# pcb.net
KiCad netlist of a schematic drawn in Altium Designer
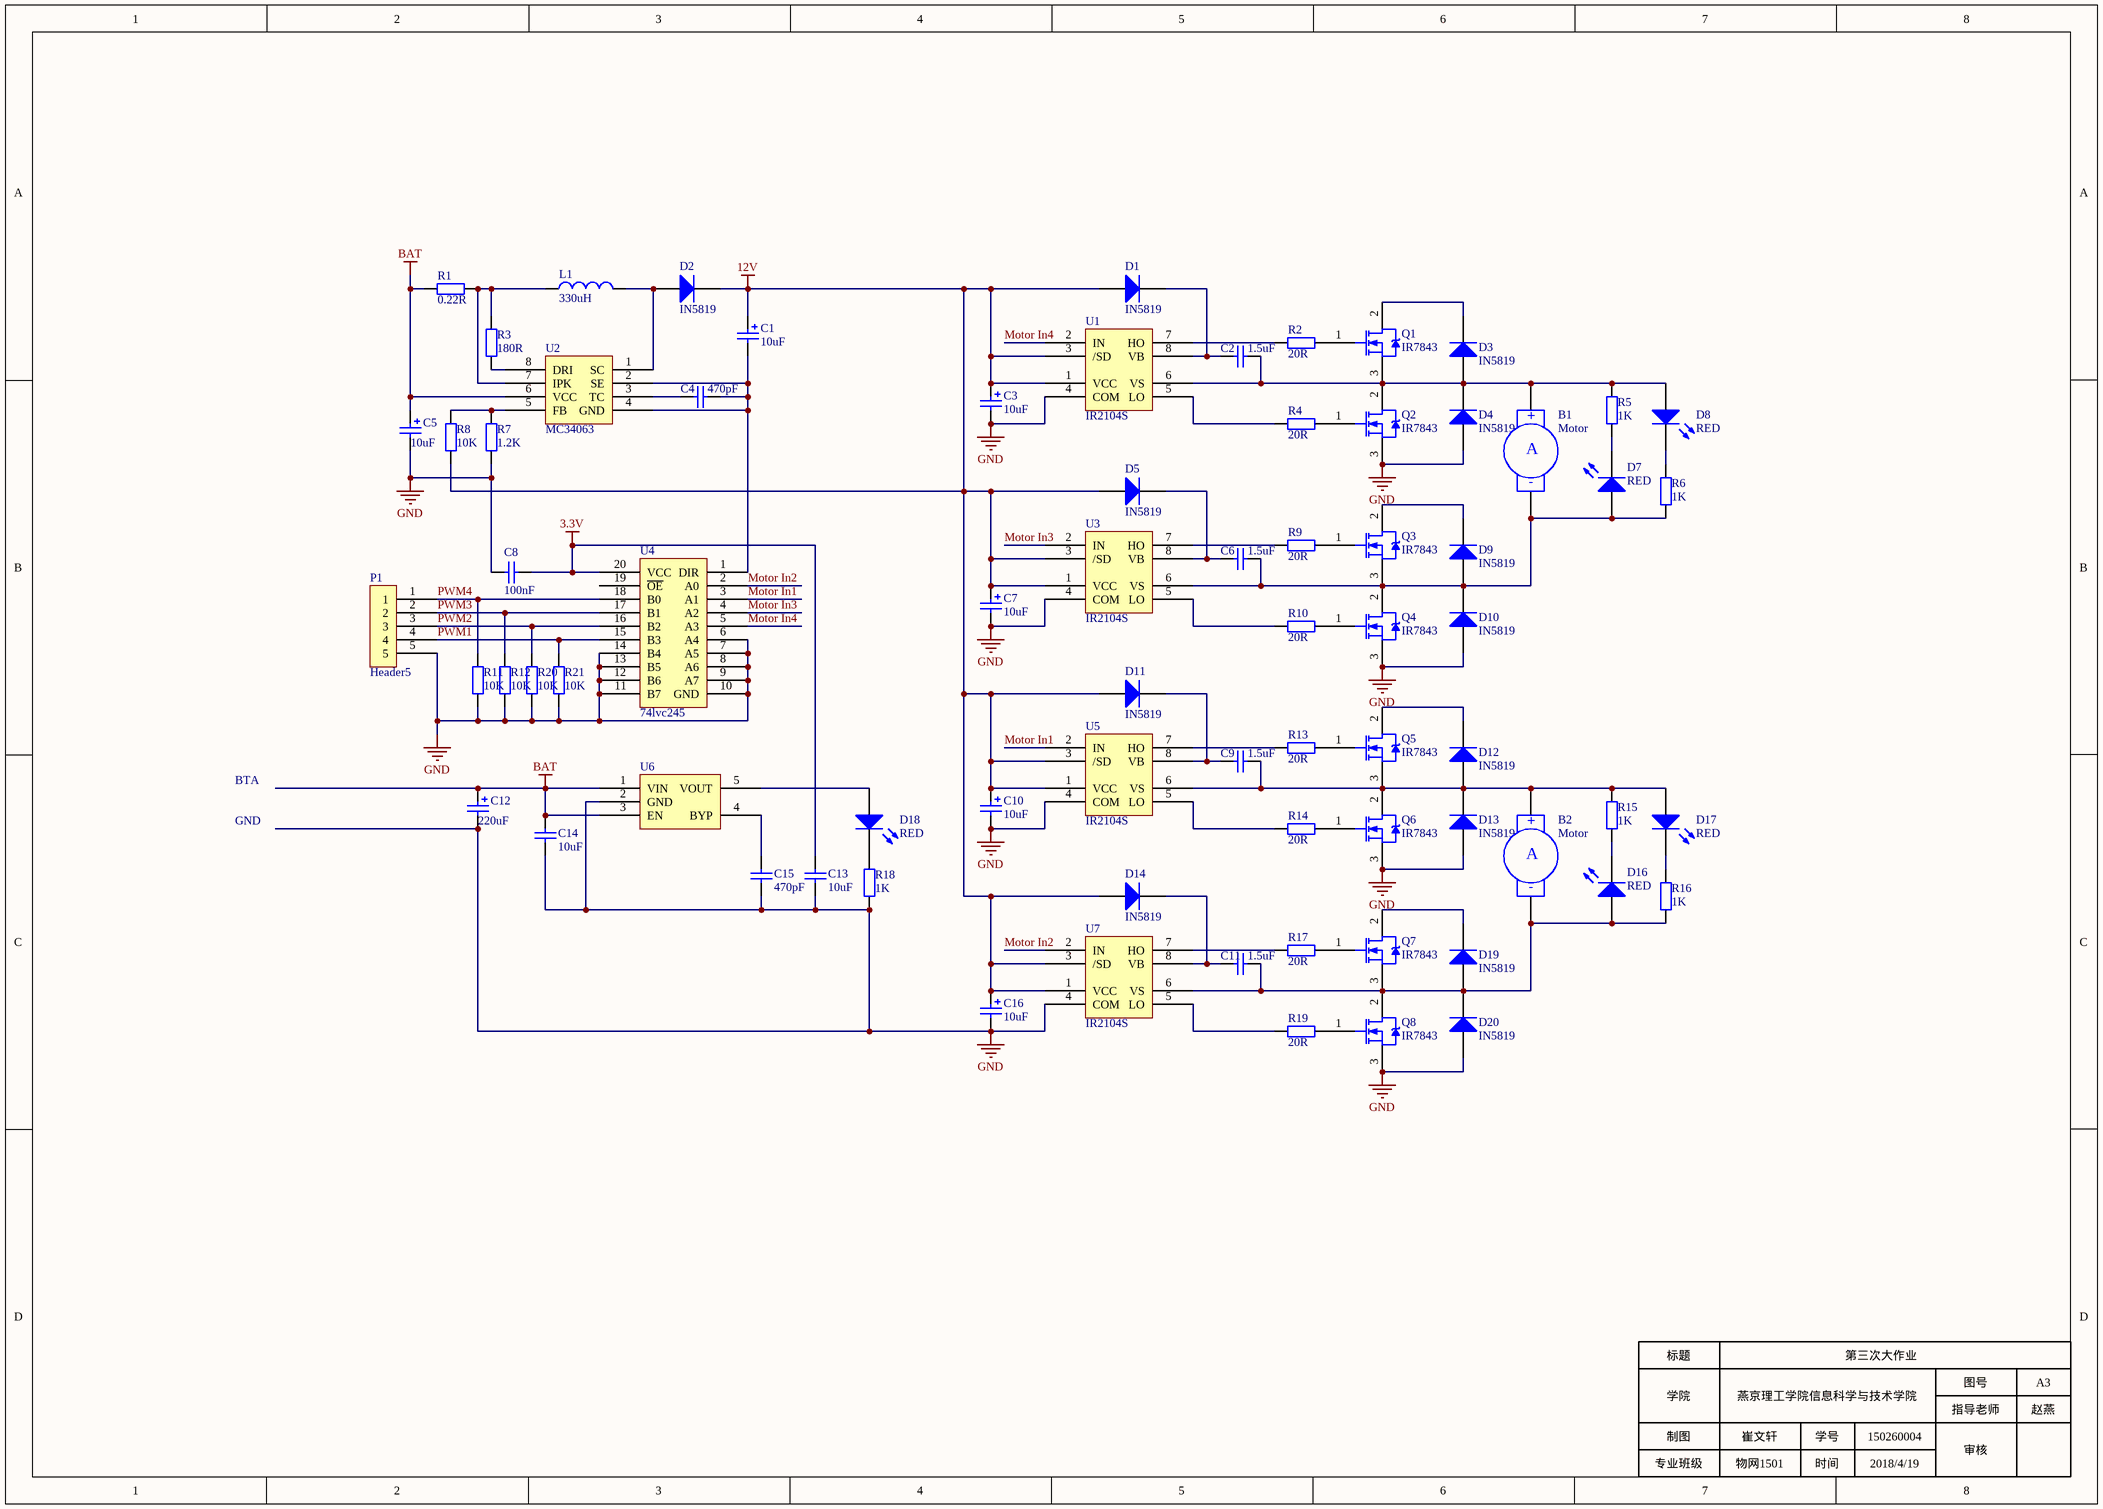
[diagram p0: pcb大作业.SchDoc]

(export (version "E")
  (design (tool "Eeschema 10.0.6"))
  (components
    (comp (ref "B1")
      (value "Motor")
      (footprint "RAD-0.4")
      (description "Servo Motor")
      (fields (field (name "PUBLISHER") "Altium Limited"))
      (libsource (lib "Miscellaneous Devices") (part "Motor Servo"))
    )
    (comp (ref "B2")
      (value "Motor")
      (footprint "RAD-0.4")
      (description "Servo Motor")
      (fields (field (name "PUBLISHER") "Altium Limited"))
      (libsource (lib "Miscellaneous Devices") (part "Motor Servo"))
    )
    (comp (ref "C1")
      (value "10uF")
      (footprint "POLAR0.8")
      (description "Polarized Capacitor (Axial)")
      (fields (field (name "Comment") "Cap Pol2") (field (name "PUBLISHER") "Altium Limited"))
      (libsource (lib "Miscellaneous Devices") (part "Cap Pol2"))
    )
    (comp (ref "C2")
      (value "1.5uF")
      (footprint "RAD-0.3")
      (description "Capacitor")
      (fields (field (name "Comment") "Cap") (field (name "PUBLISHER") "Altium Limited"))
      (libsource (lib "Miscellaneous Devices") (part "Cap"))
    )
    (comp (ref "C3")
      (value "10uF")
      (footprint "POLAR0.8")
      (description "Polarized Capacitor (Axial)")
      (fields (field (name "Comment") "Cap Pol2") (field (name "PUBLISHER") "Altium Limited"))
      (libsource (lib "Miscellaneous Devices") (part "Cap Pol2"))
    )
    (comp (ref "C4")
      (value "470pF")
      (footprint "RAD-0.3")
      (description "Capacitor")
      (fields (field (name "Comment") "Cap") (field (name "PUBLISHER") "Altium Limited"))
      (libsource (lib "Miscellaneous Devices") (part "Cap"))
    )
    (comp (ref "C5")
      (value "10uF")
      (footprint "POLAR0.8")
      (description "Polarized Capacitor (Axial)")
      (fields (field (name "Comment") "Cap Pol2") (field (name "PUBLISHER") "Altium Limited"))
      (libsource (lib "Miscellaneous Devices") (part "Cap Pol2"))
    )
    (comp (ref "C6")
      (value "1.5uF")
      (footprint "RAD-0.3")
      (description "Capacitor")
      (fields (field (name "Comment") "Cap") (field (name "PUBLISHER") "Altium Limited"))
      (libsource (lib "Miscellaneous Devices") (part "Cap"))
    )
    (comp (ref "C7")
      (value "10uF")
      (footprint "POLAR0.8")
      (description "Polarized Capacitor (Axial)")
      (fields (field (name "Comment") "Cap Pol2") (field (name "PUBLISHER") "Altium Limited"))
      (libsource (lib "Miscellaneous Devices") (part "Cap Pol2"))
    )
    (comp (ref "C8")
      (value "100nF")
      (footprint "RAD-0.3")
      (description "Capacitor")
      (fields (field (name "Comment") "Cap") (field (name "PUBLISHER") "Altium Limited"))
      (libsource (lib "Miscellaneous Devices") (part "Cap"))
    )
    (comp (ref "C9")
      (value "1.5uF")
      (footprint "RAD-0.3")
      (description "Capacitor")
      (fields (field (name "Comment") "Cap") (field (name "PUBLISHER") "Altium Limited"))
      (libsource (lib "Miscellaneous Devices") (part "Cap"))
    )
    (comp (ref "C10")
      (value "10uF")
      (footprint "POLAR0.8")
      (description "Polarized Capacitor (Axial)")
      (fields (field (name "Comment") "Cap Pol2") (field (name "PUBLISHER") "Altium Limited"))
      (libsource (lib "Miscellaneous Devices") (part "Cap Pol2"))
    )
    (comp (ref "C11")
      (value "1.5uF")
      (footprint "RAD-0.3")
      (description "Capacitor")
      (fields (field (name "Comment") "Cap") (field (name "PUBLISHER") "Altium Limited"))
      (libsource (lib "Miscellaneous Devices") (part "Cap"))
    )
    (comp (ref "C12")
      (value "220uF")
      (footprint "POLAR0.8")
      (description "Polarized Capacitor (Axial)")
      (fields (field (name "Comment") "Cap Pol2") (field (name "PUBLISHER") "Altium Limited"))
      (libsource (lib "Miscellaneous Devices") (part "Cap Pol2"))
    )
    (comp (ref "C13")
      (value "10uF")
      (footprint "RAD-0.3")
      (description "Capacitor")
      (fields (field (name "Comment") "Cap") (field (name "PUBLISHER") "Altium Limited"))
      (libsource (lib "Miscellaneous Devices") (part "Cap"))
    )
    (comp (ref "C14")
      (value "10uF")
      (footprint "RAD-0.3")
      (description "Capacitor")
      (fields (field (name "Comment") "Cap") (field (name "PUBLISHER") "Altium Limited"))
      (libsource (lib "Miscellaneous Devices") (part "Cap"))
    )
    (comp (ref "C15")
      (value "470pF")
      (footprint "RAD-0.3")
      (description "Capacitor")
      (fields (field (name "Comment") "Cap") (field (name "PUBLISHER") "Altium Limited"))
      (libsource (lib "Miscellaneous Devices") (part "Cap"))
    )
    (comp (ref "C16")
      (value "10uF")
      (footprint "POLAR0.8")
      (description "Polarized Capacitor (Axial)")
      (fields (field (name "Comment") "Cap Pol2") (field (name "PUBLISHER") "Altium Limited"))
      (libsource (lib "Miscellaneous Devices") (part "Cap Pol2"))
    )
    (comp (ref "D1")
      (value "IN5819")
      (footprint "SMC")
      (description "Default Diode")
      (fields (field (name "PUBLISHER") "Altium Limited"))
      (libsource (lib "Miscellaneous Devices") (part "Diode"))
    )
    (comp (ref "D2")
      (value "IN5819")
      (footprint "SMC")
      (description "Default Diode")
      (fields (field (name "PUBLISHER") "Altium Limited"))
      (libsource (lib "Miscellaneous Devices") (part "Diode"))
    )
    (comp (ref "D3")
      (value "IN5819")
      (footprint "SMC")
      (description "Default Diode")
      (fields (field (name "PUBLISHER") "Altium Limited"))
      (libsource (lib "Miscellaneous Devices") (part "Diode"))
    )
    (comp (ref "D4")
      (value "IN5819")
      (footprint "SMC")
      (description "Default Diode")
      (fields (field (name "PUBLISHER") "Altium Limited"))
      (libsource (lib "Miscellaneous Devices") (part "Diode"))
    )
    (comp (ref "D5")
      (value "IN5819")
      (footprint "SMC")
      (description "Default Diode")
      (fields (field (name "PUBLISHER") "Altium Limited"))
      (libsource (lib "Miscellaneous Devices") (part "Diode"))
    )
    (comp (ref "D7")
      (value "RED")
      (footprint "LED-0")
      (description "Typical INFRARED GaAs LED")
      (fields (field (name "PUBLISHER") "Altium Limited"))
      (libsource (lib "Miscellaneous Devices") (part "LED0"))
    )
    (comp (ref "D8")
      (value "RED")
      (footprint "LED-0")
      (description "Typical INFRARED GaAs LED")
      (fields (field (name "PUBLISHER") "Altium Limited"))
      (libsource (lib "Miscellaneous Devices") (part "LED0"))
    )
    (comp (ref "D9")
      (value "IN5819")
      (footprint "SMC")
      (description "Default Diode")
      (fields (field (name "PUBLISHER") "Altium Limited"))
      (libsource (lib "Miscellaneous Devices") (part "Diode"))
    )
    (comp (ref "D10")
      (value "IN5819")
      (footprint "SMC")
      (description "Default Diode")
      (fields (field (name "PUBLISHER") "Altium Limited"))
      (libsource (lib "Miscellaneous Devices") (part "Diode"))
    )
    (comp (ref "D11")
      (value "IN5819")
      (footprint "SMC")
      (description "Default Diode")
      (fields (field (name "PUBLISHER") "Altium Limited"))
      (libsource (lib "Miscellaneous Devices") (part "Diode"))
    )
    (comp (ref "D12")
      (value "IN5819")
      (footprint "SMC")
      (description "Default Diode")
      (fields (field (name "PUBLISHER") "Altium Limited"))
      (libsource (lib "Miscellaneous Devices") (part "Diode"))
    )
    (comp (ref "D13")
      (value "IN5819")
      (footprint "SMC")
      (description "Default Diode")
      (fields (field (name "PUBLISHER") "Altium Limited"))
      (libsource (lib "Miscellaneous Devices") (part "Diode"))
    )
    (comp (ref "D14")
      (value "IN5819")
      (footprint "SMC")
      (description "Default Diode")
      (fields (field (name "PUBLISHER") "Altium Limited"))
      (libsource (lib "Miscellaneous Devices") (part "Diode"))
    )
    (comp (ref "D16")
      (value "RED")
      (footprint "LED-0")
      (description "Typical INFRARED GaAs LED")
      (fields (field (name "PUBLISHER") "Altium Limited"))
      (libsource (lib "Miscellaneous Devices") (part "LED0"))
    )
    (comp (ref "D17")
      (value "RED")
      (footprint "LED-0")
      (description "Typical INFRARED GaAs LED")
      (fields (field (name "PUBLISHER") "Altium Limited"))
      (libsource (lib "Miscellaneous Devices") (part "LED0"))
    )
    (comp (ref "D18")
      (value "RED")
      (footprint "LED-0")
      (description "Typical INFRARED GaAs LED")
      (fields (field (name "PUBLISHER") "Altium Limited"))
      (libsource (lib "Miscellaneous Devices") (part "LED0"))
    )
    (comp (ref "D19")
      (value "IN5819")
      (footprint "SMC")
      (description "Default Diode")
      (fields (field (name "PUBLISHER") "Altium Limited"))
      (libsource (lib "Miscellaneous Devices") (part "Diode"))
    )
    (comp (ref "D20")
      (value "IN5819")
      (footprint "SMC")
      (description "Default Diode")
      (fields (field (name "PUBLISHER") "Altium Limited"))
      (libsource (lib "Miscellaneous Devices") (part "Diode"))
    )
    (comp (ref "L1")
      (value "330uH")
      (footprint "0402-A")
      (description "Inductor")
      (fields (field (name "PUBLISHER") "Altium Limited"))
      (libsource (lib "Miscellaneous Devices") (part "Inductor"))
    )
    (comp (ref "P1") (value "Header5") (footprint "Header5") (libsource (lib "CWX") (part "Header5")))
    (comp (ref "Q1")
      (value "IR7843")
      (footprint "TO-220AB")
      (description "N-Channel Power MOSFET")
      (fields (field (name "PUBLISHER") "Altium Limited"))
      (libsource (lib "Miscellaneous Devices") (part "NMOS-2"))
    )
    (comp (ref "Q2")
      (value "IR7843")
      (footprint "TO-220AB")
      (description "N-Channel Power MOSFET")
      (fields (field (name "PUBLISHER") "Altium Limited"))
      (libsource (lib "Miscellaneous Devices") (part "NMOS-2"))
    )
    (comp (ref "Q3")
      (value "IR7843")
      (footprint "TO-220AB")
      (description "N-Channel Power MOSFET")
      (fields (field (name "PUBLISHER") "Altium Limited"))
      (libsource (lib "Miscellaneous Devices") (part "NMOS-2"))
    )
    (comp (ref "Q4")
      (value "IR7843")
      (footprint "TO-220AB")
      (description "N-Channel Power MOSFET")
      (fields (field (name "PUBLISHER") "Altium Limited"))
      (libsource (lib "Miscellaneous Devices") (part "NMOS-2"))
    )
    (comp (ref "Q5")
      (value "IR7843")
      (footprint "TO-220AB")
      (description "N-Channel Power MOSFET")
      (fields (field (name "PUBLISHER") "Altium Limited"))
      (libsource (lib "Miscellaneous Devices") (part "NMOS-2"))
    )
    (comp (ref "Q6")
      (value "IR7843")
      (footprint "TO-220AB")
      (description "N-Channel Power MOSFET")
      (fields (field (name "PUBLISHER") "Altium Limited"))
      (libsource (lib "Miscellaneous Devices") (part "NMOS-2"))
    )
    (comp (ref "Q7")
      (value "IR7843")
      (footprint "TO-220AB")
      (description "N-Channel Power MOSFET")
      (fields (field (name "PUBLISHER") "Altium Limited"))
      (libsource (lib "Miscellaneous Devices") (part "NMOS-2"))
    )
    (comp (ref "Q8")
      (value "IR7843")
      (footprint "TO-220AB")
      (description "N-Channel Power MOSFET")
      (fields (field (name "PUBLISHER") "Altium Limited"))
      (libsource (lib "Miscellaneous Devices") (part "NMOS-2"))
    )
    (comp (ref "R1")
      (value "0.22R")
      (footprint "AXIAL-0.4")
      (description "Resistor")
      (fields (field (name "Comment") "Res2") (field (name "PUBLISHER") "Altium Limited"))
      (libsource (lib "") (part "Res2_1"))
    )
    (comp (ref "R2")
      (value "20R")
      (footprint "AXIAL-0.4")
      (description "Resistor")
      (fields (field (name "Comment") "Res2") (field (name "PUBLISHER") "Altium Limited"))
      (libsource (lib "") (part "Res2_1"))
    )
    (comp (ref "R3")
      (value "180R")
      (footprint "AXIAL-0.4")
      (description "Resistor")
      (fields (field (name "Comment") "Res2") (field (name "PUBLISHER") "Altium Limited"))
      (libsource (lib "Miscellaneous Devices") (part "Res2"))
    )
    (comp (ref "R4")
      (value "20R")
      (footprint "AXIAL-0.4")
      (description "Resistor")
      (fields (field (name "Comment") "Res2") (field (name "PUBLISHER") "Altium Limited"))
      (libsource (lib "") (part "Res2_1"))
    )
    (comp (ref "R5")
      (value "1K")
      (footprint "AXIAL-0.4")
      (description "Resistor")
      (fields (field (name "Comment") "Res2") (field (name "PUBLISHER") "Altium Limited"))
      (libsource (lib "Miscellaneous Devices") (part "Res2"))
    )
    (comp (ref "R6")
      (value "1K")
      (footprint "AXIAL-0.4")
      (description "Resistor")
      (fields (field (name "Comment") "Res2") (field (name "PUBLISHER") "Altium Limited"))
      (libsource (lib "Miscellaneous Devices") (part "Res2"))
    )
    (comp (ref "R7")
      (value "1.2K")
      (footprint "AXIAL-0.4")
      (description "Resistor")
      (fields (field (name "Comment") "Res2") (field (name "PUBLISHER") "Altium Limited"))
      (libsource (lib "Miscellaneous Devices") (part "Res2"))
    )
    (comp (ref "R8")
      (value "10K")
      (footprint "AXIAL-0.4")
      (description "Resistor")
      (fields (field (name "Comment") "Res2") (field (name "PUBLISHER") "Altium Limited"))
      (libsource (lib "Miscellaneous Devices") (part "Res2"))
    )
    (comp (ref "R9")
      (value "20R")
      (footprint "AXIAL-0.4")
      (description "Resistor")
      (fields (field (name "Comment") "Res2") (field (name "PUBLISHER") "Altium Limited"))
      (libsource (lib "") (part "Res2_1"))
    )
    (comp (ref "R10")
      (value "20R")
      (footprint "AXIAL-0.4")
      (description "Resistor")
      (fields (field (name "Comment") "Res2") (field (name "PUBLISHER") "Altium Limited"))
      (libsource (lib "") (part "Res2_1"))
    )
    (comp (ref "R11")
      (value "10K")
      (footprint "AXIAL-0.4")
      (description "Resistor")
      (fields (field (name "Comment") "Res2") (field (name "PUBLISHER") "Altium Limited"))
      (libsource (lib "Miscellaneous Devices") (part "Res2"))
    )
    (comp (ref "R12")
      (value "10K")
      (footprint "AXIAL-0.4")
      (description "Resistor")
      (fields (field (name "Comment") "Res2") (field (name "PUBLISHER") "Altium Limited"))
      (libsource (lib "Miscellaneous Devices") (part "Res2"))
    )
    (comp (ref "R13")
      (value "20R")
      (footprint "AXIAL-0.4")
      (description "Resistor")
      (fields (field (name "Comment") "Res2") (field (name "PUBLISHER") "Altium Limited"))
      (libsource (lib "") (part "Res2_1"))
    )
    (comp (ref "R14")
      (value "20R")
      (footprint "AXIAL-0.4")
      (description "Resistor")
      (fields (field (name "Comment") "Res2") (field (name "PUBLISHER") "Altium Limited"))
      (libsource (lib "") (part "Res2_1"))
    )
    (comp (ref "R15")
      (value "1K")
      (footprint "AXIAL-0.4")
      (description "Resistor")
      (fields (field (name "Comment") "Res2") (field (name "PUBLISHER") "Altium Limited"))
      (libsource (lib "Miscellaneous Devices") (part "Res2"))
    )
    (comp (ref "R16")
      (value "1K")
      (footprint "AXIAL-0.4")
      (description "Resistor")
      (fields (field (name "Comment") "Res2") (field (name "PUBLISHER") "Altium Limited"))
      (libsource (lib "Miscellaneous Devices") (part "Res2"))
    )
    (comp (ref "R17")
      (value "20R")
      (footprint "AXIAL-0.4")
      (description "Resistor")
      (fields (field (name "Comment") "Res2") (field (name "PUBLISHER") "Altium Limited"))
      (libsource (lib "") (part "Res2_1"))
    )
    (comp (ref "R18")
      (value "1K")
      (footprint "AXIAL-0.4")
      (description "Resistor")
      (fields (field (name "Comment") "Res2") (field (name "PUBLISHER") "Altium Limited"))
      (libsource (lib "Miscellaneous Devices") (part "Res2"))
    )
    (comp (ref "R19")
      (value "20R")
      (footprint "AXIAL-0.4")
      (description "Resistor")
      (fields (field (name "Comment") "Res2") (field (name "PUBLISHER") "Altium Limited"))
      (libsource (lib "") (part "Res2_1"))
    )
    (comp (ref "R20")
      (value "10K")
      (footprint "AXIAL-0.4")
      (description "Resistor")
      (fields (field (name "Comment") "Res2") (field (name "PUBLISHER") "Altium Limited"))
      (libsource (lib "Miscellaneous Devices") (part "Res2"))
    )
    (comp (ref "R21")
      (value "10K")
      (footprint "AXIAL-0.4")
      (description "Resistor")
      (fields (field (name "Comment") "Res2") (field (name "PUBLISHER") "Altium Limited"))
      (libsource (lib "Miscellaneous Devices") (part "Res2"))
    )
    (comp (ref "U1") (value "IR2104S") (footprint "ir2104s") (libsource (lib "CWX") (part "IR2104S")))
    (comp (ref "U2") (value "MC34063") (footprint "MC34063") (libsource (lib "CWX") (part "MC34063")))
    (comp (ref "U3") (value "IR2104S") (footprint "ir2104s") (libsource (lib "CWX") (part "IR2104S")))
    (comp (ref "U4") (value "74lvc245") (footprint "74lvc245") (libsource (lib "CWX") (part "74lvc245")))
    (comp (ref "U5") (value "IR2104S") (footprint "ir2104s") (libsource (lib "CWX") (part "IR2104S")))
    (comp (ref "U6") (value "U6") (footprint "u6") (libsource (lib "CWX") (part "U6")))
    (comp (ref "U7") (value "IR2104S") (footprint "ir2104s") (libsource (lib "CWX") (part "IR2104S")))
  )
  (nets
    (net (code "1") (name "/Motor In1") (class "Default")
      (node (ref "U4") (pin "3") (pinfunction "A1_3") (pintype "passive"))
      (node (ref "U5") (pin "2") (pinfunction "IN_2") (pintype "passive"))
    )
    (net (code "2") (name "/Motor In2") (class "Default")
      (node (ref "U4") (pin "2") (pinfunction "A0_2") (pintype "passive"))
      (node (ref "U7") (pin "2") (pinfunction "IN_2") (pintype "passive"))
    )
    (net (code "3") (name "/Motor In3") (class "Default")
      (node (ref "U3") (pin "2") (pinfunction "IN_2") (pintype "passive"))
      (node (ref "U4") (pin "4") (pinfunction "A2_4") (pintype "passive"))
    )
    (net (code "4") (name "/Motor In4") (class "Default")
      (node (ref "U1") (pin "2") (pinfunction "IN_2") (pintype "passive"))
      (node (ref "U4") (pin "5") (pinfunction "A3_5") (pintype "passive"))
    )
    (net (code "5") (name "/PWM1") (class "Default")
      (node (ref "P1") (pin "4") (pinfunction "4_4") (pintype "passive"))
      (node (ref "R21") (pin "2") (pinfunction "2_2") (pintype "passive"))
      (node (ref "U4") (pin "15") (pinfunction "B3_15") (pintype "passive"))
    )
    (net (code "6") (name "/PWM2") (class "Default")
      (node (ref "P1") (pin "3") (pinfunction "3_3") (pintype "passive"))
      (node (ref "R20") (pin "2") (pinfunction "2_2") (pintype "passive"))
      (node (ref "U4") (pin "16") (pinfunction "B2_16") (pintype "passive"))
    )
    (net (code "7") (name "/PWM3") (class "Default")
      (node (ref "P1") (pin "2") (pinfunction "2_2") (pintype "passive"))
      (node (ref "R12") (pin "2") (pinfunction "2_2") (pintype "passive"))
      (node (ref "U4") (pin "17") (pinfunction "B1_17") (pintype "passive"))
    )
    (net (code "8") (name "/PWM4") (class "Default")
      (node (ref "P1") (pin "1") (pinfunction "1_1") (pintype "passive"))
      (node (ref "R11") (pin "2") (pinfunction "2_2") (pintype "passive"))
      (node (ref "U4") (pin "18") (pinfunction "B0_18") (pintype "passive"))
    )
    (net (code "9") (name "3.3V") (class "Default")
      (node (ref "C13") (pin "2") (pinfunction "2_2") (pintype "passive"))
      (node (ref "C8") (pin "2") (pinfunction "2_2") (pintype "passive"))
      (node (ref "U4") (pin "20") (pinfunction "VCC_20") (pintype "passive"))
    )
    (net (code "10") (name "12V") (class "Default")
      (node (ref "C1") (pin "1") (pinfunction "1_1") (pintype "passive"))
      (node (ref "C10") (pin "1") (pinfunction "1_1") (pintype "passive"))
      (node (ref "C16") (pin "1") (pinfunction "1_1") (pintype "passive"))
      (node (ref "C3") (pin "1") (pinfunction "1_1") (pintype "passive"))
      (node (ref "C7") (pin "1") (pinfunction "1_1") (pintype "passive"))
      (node (ref "D1") (pin "1") (pinfunction "A_1") (pintype "passive"))
      (node (ref "D11") (pin "1") (pinfunction "A_1") (pintype "passive"))
      (node (ref "D14") (pin "1") (pinfunction "A_1") (pintype "passive"))
      (node (ref "D2") (pin "2") (pinfunction "K_2") (pintype "passive"))
      (node (ref "D5") (pin "1") (pinfunction "A_1") (pintype "passive"))
      (node (ref "R8") (pin "1") (pinfunction "1_1") (pintype "passive"))
      (node (ref "U1") (pin "1") (pinfunction "VCC_1") (pintype "passive"))
      (node (ref "U1") (pin "3") (pinfunction "/SD_3") (pintype "passive"))
      (node (ref "U3") (pin "1") (pinfunction "VCC_1") (pintype "passive"))
      (node (ref "U3") (pin "3") (pinfunction "/SD_3") (pintype "passive"))
      (node (ref "U5") (pin "1") (pinfunction "VCC_1") (pintype "passive"))
      (node (ref "U5") (pin "3") (pinfunction "/SD_3") (pintype "passive"))
      (node (ref "U7") (pin "1") (pinfunction "VCC_1") (pintype "passive"))
      (node (ref "U7") (pin "3") (pinfunction "/SD_3") (pintype "passive"))
    )
    (net (code "11") (name "BAT") (class "Default")
      (node (ref "C12") (pin "1") (pinfunction "1_1") (pintype "passive"))
      (node (ref "C14") (pin "2") (pinfunction "2_2") (pintype "passive"))
      (node (ref "C5") (pin "1") (pinfunction "1_1") (pintype "passive"))
      (node (ref "R1") (pin "1") (pinfunction "1_1") (pintype "passive"))
      (node (ref "U2") (pin "6") (pinfunction "VCC_6") (pintype "passive"))
      (node (ref "U6") (pin "1") (pinfunction "VIN_1") (pintype "passive"))
      (node (ref "U6") (pin "3") (pinfunction "EN_3") (pintype "passive"))
    )
    (net (code "12") (name "GND") (class "Default")
      (node (ref "C10") (pin "2") (pinfunction "2_2") (pintype "passive"))
      (node (ref "C12") (pin "2") (pinfunction "2_2") (pintype "passive"))
      (node (ref "C13") (pin "1") (pinfunction "1_1") (pintype "passive"))
      (node (ref "C14") (pin "1") (pinfunction "1_1") (pintype "passive"))
      (node (ref "C15") (pin "1") (pinfunction "1_1") (pintype "passive"))
      (node (ref "C16") (pin "2") (pinfunction "2_2") (pintype "passive"))
      (node (ref "C3") (pin "2") (pinfunction "2_2") (pintype "passive"))
      (node (ref "C5") (pin "2") (pinfunction "2_2") (pintype "passive"))
      (node (ref "C7") (pin "2") (pinfunction "2_2") (pintype "passive"))
      (node (ref "C8") (pin "1") (pinfunction "1_1") (pintype "passive"))
      (node (ref "D10") (pin "1") (pinfunction "A_1") (pintype "passive"))
      (node (ref "D13") (pin "1") (pinfunction "A_1") (pintype "passive"))
      (node (ref "D20") (pin "1") (pinfunction "A_1") (pintype "passive"))
      (node (ref "D4") (pin "1") (pinfunction "A_1") (pintype "passive"))
      (node (ref "P1") (pin "5") (pinfunction "5_5") (pintype "passive"))
      (node (ref "Q2") (pin "3") (pinfunction "S_3") (pintype "passive"))
      (node (ref "Q4") (pin "3") (pinfunction "S_3") (pintype "passive"))
      (node (ref "Q6") (pin "3") (pinfunction "S_3") (pintype "passive"))
      (node (ref "Q8") (pin "3") (pinfunction "S_3") (pintype "passive"))
      (node (ref "R11") (pin "1") (pinfunction "1_1") (pintype "passive"))
      (node (ref "R12") (pin "1") (pinfunction "1_1") (pintype "passive"))
      (node (ref "R18") (pin "1") (pinfunction "1_1") (pintype "passive"))
      (node (ref "R20") (pin "1") (pinfunction "1_1") (pintype "passive"))
      (node (ref "R21") (pin "1") (pinfunction "1_1") (pintype "passive"))
      (node (ref "R7") (pin "1") (pinfunction "1_1") (pintype "passive"))
      (node (ref "U1") (pin "4") (pinfunction "COM_4") (pintype "passive"))
      (node (ref "U3") (pin "4") (pinfunction "COM_4") (pintype "passive"))
      (node (ref "U4") (pin "10") (pinfunction "GND_10") (pintype "passive"))
      (node (ref "U4") (pin "11") (pinfunction "B7_11") (pintype "passive"))
      (node (ref "U4") (pin "12") (pinfunction "B6_12") (pintype "passive"))
      (node (ref "U4") (pin "13") (pinfunction "B5_13") (pintype "passive"))
      (node (ref "U4") (pin "14") (pinfunction "B4_14") (pintype "passive"))
      (node (ref "U4") (pin "6") (pinfunction "A4_6") (pintype "passive"))
      (node (ref "U4") (pin "7") (pinfunction "A5_7") (pintype "passive"))
      (node (ref "U4") (pin "8") (pinfunction "A6_8") (pintype "passive"))
      (node (ref "U4") (pin "9") (pinfunction "A7_9") (pintype "passive"))
      (node (ref "U5") (pin "4") (pinfunction "COM_4") (pintype "passive"))
      (node (ref "U6") (pin "2") (pinfunction "GND_2") (pintype "passive"))
      (node (ref "U7") (pin "4") (pinfunction "COM_4") (pintype "passive"))
    )
    (net (code "13") (name "Net-(B1-+)") (class "Default")
      (node (ref "B1") (pin "1") (pinfunction "+_1") (pintype "passive"))
      (node (ref "C2") (pin "2") (pinfunction "2_2") (pintype "passive"))
      (node (ref "D3") (pin "1") (pinfunction "A_1") (pintype "passive"))
      (node (ref "D4") (pin "2") (pinfunction "K_2") (pintype "passive"))
      (node (ref "D8") (pin "1") (pinfunction "A_1") (pintype "passive"))
      (node (ref "Q1") (pin "3") (pinfunction "S_3") (pintype "passive"))
      (node (ref "Q2") (pin "2") (pinfunction "D_2") (pintype "passive"))
      (node (ref "R5") (pin "2") (pinfunction "2_2") (pintype "passive"))
      (node (ref "U1") (pin "6") (pinfunction "VS_6") (pintype "passive"))
    )
    (net (code "14") (name "Net-(B1--)") (class "Default")
      (node (ref "B1") (pin "2") (pinfunction "-_2") (pintype "passive"))
      (node (ref "C6") (pin "2") (pinfunction "2_2") (pintype "passive"))
      (node (ref "D10") (pin "2") (pinfunction "K_2") (pintype "passive"))
      (node (ref "D7") (pin "1") (pinfunction "A_1") (pintype "passive"))
      (node (ref "D9") (pin "1") (pinfunction "A_1") (pintype "passive"))
      (node (ref "Q3") (pin "3") (pinfunction "S_3") (pintype "passive"))
      (node (ref "Q4") (pin "2") (pinfunction "D_2") (pintype "passive"))
      (node (ref "R6") (pin "1") (pinfunction "1_1") (pintype "passive"))
      (node (ref "U3") (pin "6") (pinfunction "VS_6") (pintype "passive"))
    )
    (net (code "15") (name "Net-(B2-+)") (class "Default")
      (node (ref "B2") (pin "1") (pinfunction "+_1") (pintype "passive"))
      (node (ref "C9") (pin "2") (pinfunction "2_2") (pintype "passive"))
      (node (ref "D12") (pin "1") (pinfunction "A_1") (pintype "passive"))
      (node (ref "D13") (pin "2") (pinfunction "K_2") (pintype "passive"))
      (node (ref "D17") (pin "1") (pinfunction "A_1") (pintype "passive"))
      (node (ref "Q5") (pin "3") (pinfunction "S_3") (pintype "passive"))
      (node (ref "Q6") (pin "2") (pinfunction "D_2") (pintype "passive"))
      (node (ref "R15") (pin "2") (pinfunction "2_2") (pintype "passive"))
      (node (ref "U5") (pin "6") (pinfunction "VS_6") (pintype "passive"))
    )
    (net (code "16") (name "Net-(B2--)") (class "Default")
      (node (ref "B2") (pin "2") (pinfunction "-_2") (pintype "passive"))
      (node (ref "C11") (pin "2") (pinfunction "2_2") (pintype "passive"))
      (node (ref "D16") (pin "1") (pinfunction "A_1") (pintype "passive"))
      (node (ref "D19") (pin "1") (pinfunction "A_1") (pintype "passive"))
      (node (ref "D20") (pin "2") (pinfunction "K_2") (pintype "passive"))
      (node (ref "Q7") (pin "3") (pinfunction "S_3") (pintype "passive"))
      (node (ref "Q8") (pin "2") (pinfunction "D_2") (pintype "passive"))
      (node (ref "R16") (pin "1") (pinfunction "1_1") (pintype "passive"))
      (node (ref "U7") (pin "6") (pinfunction "VS_6") (pintype "passive"))
    )
    (net (code "17") (name "Net-(D1-K)") (class "Default")
      (node (ref "C2") (pin "1") (pinfunction "1_1") (pintype "passive"))
      (node (ref "D1") (pin "2") (pinfunction "K_2") (pintype "passive"))
      (node (ref "U1") (pin "8") (pinfunction "VB_8") (pintype "passive"))
    )
    (net (code "18") (name "Net-(D2-A)") (class "Default")
      (node (ref "D2") (pin "1") (pinfunction "A_1") (pintype "passive"))
      (node (ref "L1") (pin "2") (pinfunction "2_2") (pintype "passive"))
      (node (ref "U2") (pin "1") (pinfunction "SC_1") (pintype "passive"))
    )
    (net (code "19") (name "Net-(D3-K)") (class "Default")
      (node (ref "D3") (pin "2") (pinfunction "K_2") (pintype "passive"))
      (node (ref "Q1") (pin "2") (pinfunction "D_2") (pintype "passive"))
    )
    (net (code "20") (name "Net-(D5-K)") (class "Default")
      (node (ref "C6") (pin "1") (pinfunction "1_1") (pintype "passive"))
      (node (ref "D5") (pin "2") (pinfunction "K_2") (pintype "passive"))
      (node (ref "U3") (pin "8") (pinfunction "VB_8") (pintype "passive"))
    )
    (net (code "21") (name "Net-(D7-K)") (class "Default")
      (node (ref "D7") (pin "2") (pinfunction "K_2") (pintype "passive"))
      (node (ref "R5") (pin "1") (pinfunction "1_1") (pintype "passive"))
    )
    (net (code "22") (name "Net-(D8-K)") (class "Default")
      (node (ref "D8") (pin "2") (pinfunction "K_2") (pintype "passive"))
      (node (ref "R6") (pin "2") (pinfunction "2_2") (pintype "passive"))
    )
    (net (code "23") (name "Net-(D9-K)") (class "Default")
      (node (ref "D9") (pin "2") (pinfunction "K_2") (pintype "passive"))
      (node (ref "Q3") (pin "2") (pinfunction "D_2") (pintype "passive"))
    )
    (net (code "24") (name "Net-(D11-K)") (class "Default")
      (node (ref "C9") (pin "1") (pinfunction "1_1") (pintype "passive"))
      (node (ref "D11") (pin "2") (pinfunction "K_2") (pintype "passive"))
      (node (ref "U5") (pin "8") (pinfunction "VB_8") (pintype "passive"))
    )
    (net (code "25") (name "Net-(D12-K)") (class "Default")
      (node (ref "D12") (pin "2") (pinfunction "K_2") (pintype "passive"))
      (node (ref "Q5") (pin "2") (pinfunction "D_2") (pintype "passive"))
    )
    (net (code "26") (name "Net-(D14-K)") (class "Default")
      (node (ref "C11") (pin "1") (pinfunction "1_1") (pintype "passive"))
      (node (ref "D14") (pin "2") (pinfunction "K_2") (pintype "passive"))
      (node (ref "U7") (pin "8") (pinfunction "VB_8") (pintype "passive"))
    )
    (net (code "27") (name "Net-(D16-K)") (class "Default")
      (node (ref "D16") (pin "2") (pinfunction "K_2") (pintype "passive"))
      (node (ref "R15") (pin "1") (pinfunction "1_1") (pintype "passive"))
    )
    (net (code "28") (name "Net-(D17-K)") (class "Default")
      (node (ref "D17") (pin "2") (pinfunction "K_2") (pintype "passive"))
      (node (ref "R16") (pin "2") (pinfunction "2_2") (pintype "passive"))
    )
    (net (code "29") (name "Net-(D18-A)") (class "Default")
      (node (ref "D18") (pin "1") (pinfunction "A_1") (pintype "passive"))
      (node (ref "U6") (pin "5") (pinfunction "VOUT_5") (pintype "passive"))
    )
    (net (code "30") (name "Net-(D18-K)") (class "Default")
      (node (ref "D18") (pin "2") (pinfunction "K_2") (pintype "passive"))
      (node (ref "R18") (pin "2") (pinfunction "2_2") (pintype "passive"))
    )
    (net (code "31") (name "Net-(D19-K)") (class "Default")
      (node (ref "D19") (pin "2") (pinfunction "K_2") (pintype "passive"))
      (node (ref "Q7") (pin "2") (pinfunction "D_2") (pintype "passive"))
    )
    (net (code "32") (name "Net-(Q1-G)") (class "Default")
      (node (ref "Q1") (pin "1") (pinfunction "G_1") (pintype "passive"))
      (node (ref "R2") (pin "2") (pinfunction "2_2") (pintype "passive"))
    )
    (net (code "33") (name "Net-(Q2-G)") (class "Default")
      (node (ref "Q2") (pin "1") (pinfunction "G_1") (pintype "passive"))
      (node (ref "R4") (pin "2") (pinfunction "2_2") (pintype "passive"))
    )
    (net (code "34") (name "Net-(Q3-G)") (class "Default")
      (node (ref "Q3") (pin "1") (pinfunction "G_1") (pintype "passive"))
      (node (ref "R9") (pin "2") (pinfunction "2_2") (pintype "passive"))
    )
    (net (code "35") (name "Net-(Q4-G)") (class "Default")
      (node (ref "Q4") (pin "1") (pinfunction "G_1") (pintype "passive"))
      (node (ref "R10") (pin "2") (pinfunction "2_2") (pintype "passive"))
    )
    (net (code "36") (name "Net-(Q5-G)") (class "Default")
      (node (ref "Q5") (pin "1") (pinfunction "G_1") (pintype "passive"))
      (node (ref "R13") (pin "2") (pinfunction "2_2") (pintype "passive"))
    )
    (net (code "37") (name "Net-(Q6-G)") (class "Default")
      (node (ref "Q6") (pin "1") (pinfunction "G_1") (pintype "passive"))
      (node (ref "R14") (pin "2") (pinfunction "2_2") (pintype "passive"))
    )
    (net (code "38") (name "Net-(Q7-G)") (class "Default")
      (node (ref "Q7") (pin "1") (pinfunction "G_1") (pintype "passive"))
      (node (ref "R17") (pin "2") (pinfunction "2_2") (pintype "passive"))
    )
    (net (code "39") (name "Net-(Q8-G)") (class "Default")
      (node (ref "Q8") (pin "1") (pinfunction "G_1") (pintype "passive"))
      (node (ref "R19") (pin "2") (pinfunction "2_2") (pintype "passive"))
    )
    (net (code "40") (name "Net-(U1-HO)") (class "Default")
      (node (ref "R2") (pin "1") (pinfunction "1_1") (pintype "passive"))
      (node (ref "U1") (pin "7") (pinfunction "HO_7") (pintype "passive"))
    )
    (net (code "41") (name "Net-(U1-LO)") (class "Default")
      (node (ref "R4") (pin "1") (pinfunction "1_1") (pintype "passive"))
      (node (ref "U1") (pin "5") (pinfunction "LO_5") (pintype "passive"))
    )
    (net (code "42") (name "Net-(U2-DRI)") (class "Default")
      (node (ref "R3") (pin "1") (pinfunction "1_1") (pintype "passive"))
      (node (ref "U2") (pin "8") (pinfunction "DRI_8") (pintype "passive"))
    )
    (net (code "43") (name "Net-(U2-FB)") (class "Default")
      (node (ref "R7") (pin "2") (pinfunction "2_2") (pintype "passive"))
      (node (ref "R8") (pin "2") (pinfunction "2_2") (pintype "passive"))
      (node (ref "U2") (pin "5") (pinfunction "FB_5") (pintype "passive"))
    )
    (net (code "44") (name "Net-(U2-GND)") (class "Default")
      (node (ref "C1") (pin "2") (pinfunction "2_2") (pintype "passive"))
      (node (ref "C4") (pin "1") (pinfunction "1_1") (pintype "passive"))
      (node (ref "U2") (pin "2") (pinfunction "SE_2") (pintype "passive"))
      (node (ref "U2") (pin "4") (pinfunction "GND_4") (pintype "passive"))
      (node (ref "U4") (pin "1") (pinfunction "DIR_1") (pintype "passive"))
    )
    (net (code "45") (name "Net-(U2-IPK)") (class "Default")
      (node (ref "L1") (pin "1") (pinfunction "1_1") (pintype "passive"))
      (node (ref "R1") (pin "2") (pinfunction "2_2") (pintype "passive"))
      (node (ref "R3") (pin "2") (pinfunction "2_2") (pintype "passive"))
      (node (ref "U2") (pin "7") (pinfunction "IPK_7") (pintype "passive"))
    )
    (net (code "46") (name "Net-(U2-TC)") (class "Default")
      (node (ref "C4") (pin "2") (pinfunction "2_2") (pintype "passive"))
      (node (ref "U2") (pin "3") (pinfunction "TC_3") (pintype "passive"))
    )
    (net (code "47") (name "Net-(U3-HO)") (class "Default")
      (node (ref "R9") (pin "1") (pinfunction "1_1") (pintype "passive"))
      (node (ref "U3") (pin "7") (pinfunction "HO_7") (pintype "passive"))
    )
    (net (code "48") (name "Net-(U3-LO)") (class "Default")
      (node (ref "R10") (pin "1") (pinfunction "1_1") (pintype "passive"))
      (node (ref "U3") (pin "5") (pinfunction "LO_5") (pintype "passive"))
    )
    (net (code "49") (name "Net-(U5-HO)") (class "Default")
      (node (ref "R13") (pin "1") (pinfunction "1_1") (pintype "passive"))
      (node (ref "U5") (pin "7") (pinfunction "HO_7") (pintype "passive"))
    )
    (net (code "50") (name "Net-(U5-LO)") (class "Default")
      (node (ref "R14") (pin "1") (pinfunction "1_1") (pintype "passive"))
      (node (ref "U5") (pin "5") (pinfunction "LO_5") (pintype "passive"))
    )
    (net (code "51") (name "Net-(U6-BYP)") (class "Default")
      (node (ref "C15") (pin "2") (pinfunction "2_2") (pintype "passive"))
      (node (ref "U6") (pin "4") (pinfunction "BYP_4") (pintype "passive"))
    )
    (net (code "52") (name "Net-(U7-HO)") (class "Default")
      (node (ref "R17") (pin "1") (pinfunction "1_1") (pintype "passive"))
      (node (ref "U7") (pin "7") (pinfunction "HO_7") (pintype "passive"))
    )
    (net (code "53") (name "Net-(U7-LO)") (class "Default")
      (node (ref "R19") (pin "1") (pinfunction "1_1") (pintype "passive"))
      (node (ref "U7") (pin "5") (pinfunction "LO_5") (pintype "passive"))
    )
    (net (code "54") (name "unconnected-(U4-~{OE}-Pad19)") (class "Default")
      (node (ref "U4") (pin "19") (pinfunction "~{OE}_19") (pintype "passive"))
    )
  )
)
